# pure_energy.net
KiCad netlist of a schematic drawn in EAGLE
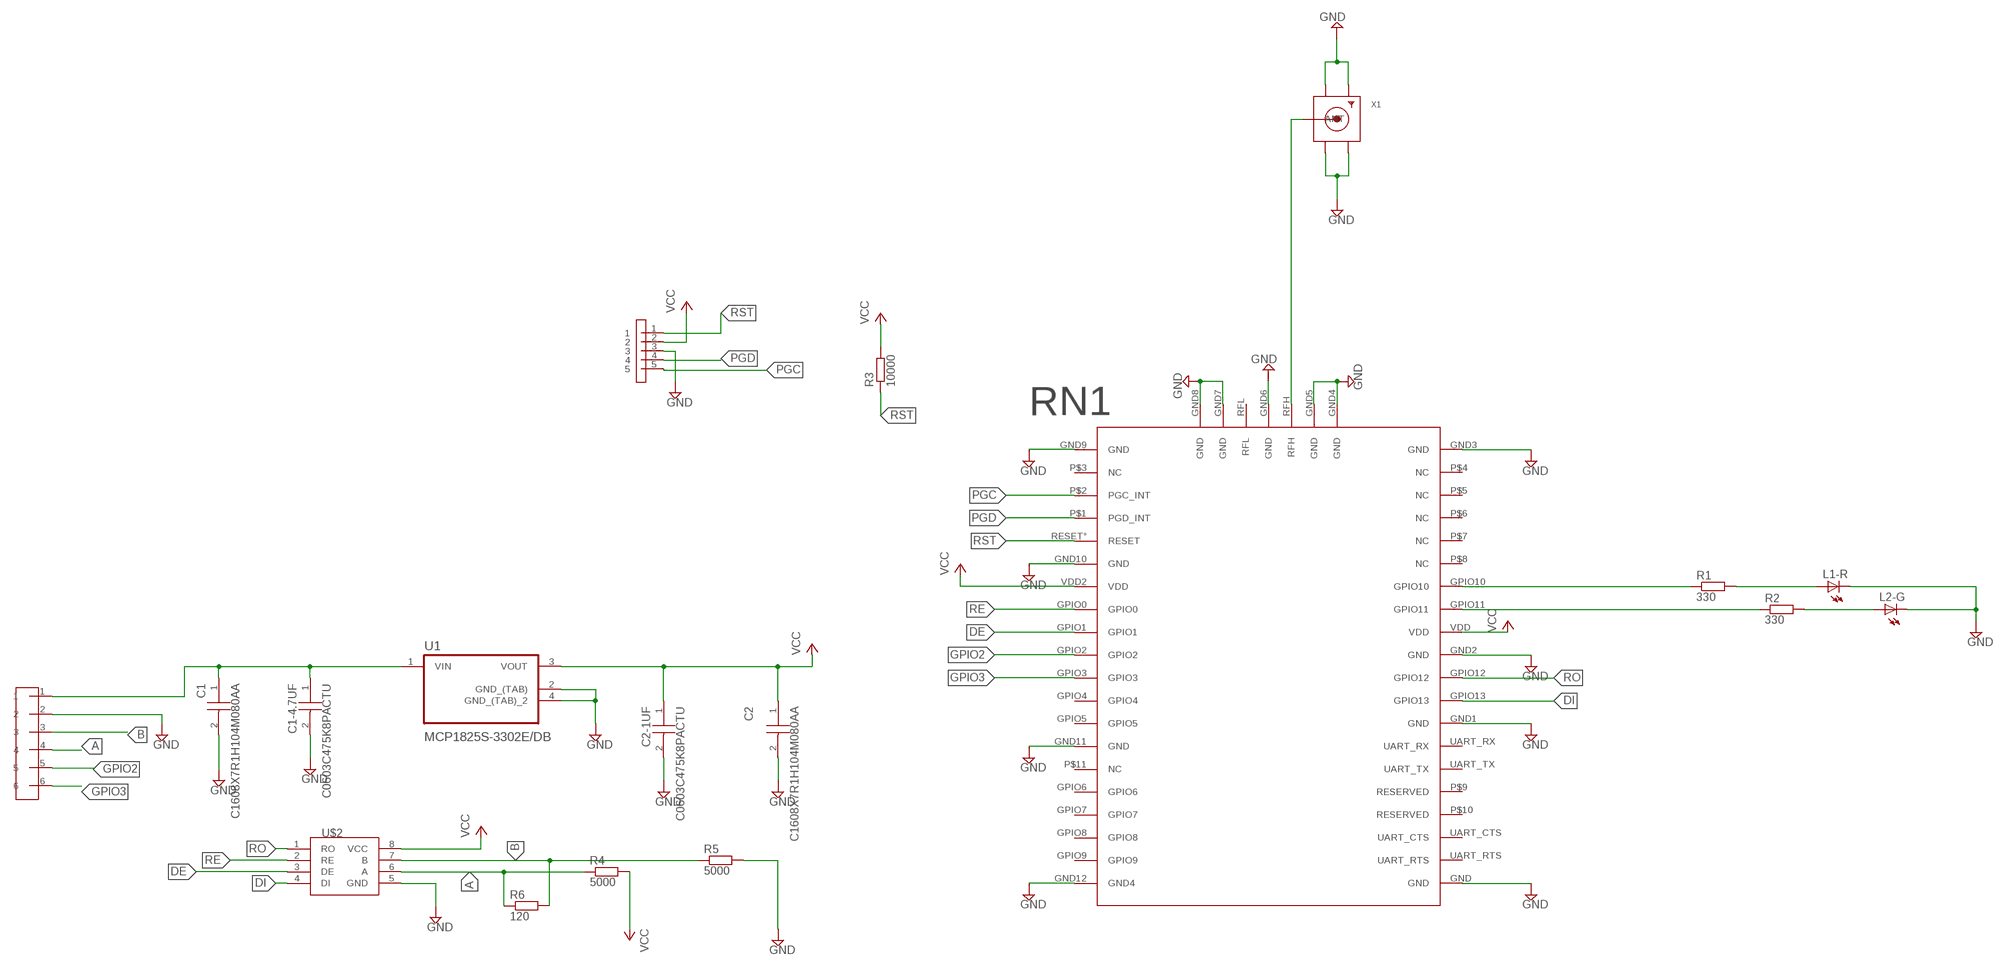
[diagram p0: schematic, sheet 1]

(export (version "E")
  (design (tool "Eeschema 10.0.6"))
  (components
    (comp (ref "C1")
      (value "C1608X7R1H104M080AA")
      (footprint "eagle-import:CAPC1608X80N")
      (fields (field (name "MOUSER_PART_NUMBER") "810-C1608X7R1H104M"))
      (libsource (lib "eagle-import") (part "C1608X7R1H104M080AA"))
    )
    (comp (ref "C1-4.7UF")
      (value "C0603C475K8PACTU")
      (footprint "eagle-import:CAPC1608X85N")
      (fields (field (name "MOUSER_PART_NUMBER") "80-C0603C475K8P"))
      (libsource (lib "eagle-import") (part "C0603C475K8PACTU"))
    )
    (comp (ref "C2")
      (value "C1608X7R1H104M080AA")
      (footprint "eagle-import:CAPC1608X80N")
      (fields (field (name "MOUSER_PART_NUMBER") "810-C1608X7R1H104M"))
      (libsource (lib "eagle-import") (part "C1608X7R1H104M080AA"))
    )
    (comp (ref "C2-1UF")
      (value "C0603C475K8PACTU")
      (footprint "eagle-import:CAPC1608X85N")
      (fields (field (name "MOUSER_PART_NUMBER") "80-C0603C475K8P"))
      (libsource (lib "eagle-import") (part "C0603C475K8PACTU"))
    )
    (comp (ref "L1-R")
      (value "LEDCHIP-LED0603")
      (footprint "eagle-import:CHIP-LED0603")
      (libsource (lib "eagle-import") (part "LEDCHIP-LED0603"))
    )
    (comp (ref "L2-G")
      (value "LEDCHIP-LED0603")
      (footprint "eagle-import:CHIP-LED0603")
      (libsource (lib "eagle-import") (part "LEDCHIP-LED0603"))
    )
    (comp (ref "R1")
      (value "330")
      (footprint "eagle-import:R0603")
      (libsource (lib "eagle-import") (part "R-EU_R0603"))
    )
    (comp (ref "R2")
      (value "330")
      (footprint "eagle-import:R0603")
      (libsource (lib "eagle-import") (part "R-EU_R0603"))
    )
    (comp (ref "R3")
      (value "10000")
      (footprint "eagle-import:R0603")
      (libsource (lib "eagle-import") (part "R-EU_R0603"))
    )
    (comp (ref "R4")
      (value "5000")
      (footprint "eagle-import:R0805")
      (libsource (lib "eagle-import") (part "R-EU_R0805"))
    )
    (comp (ref "R5")
      (value "5000")
      (footprint "eagle-import:R0805")
      (libsource (lib "eagle-import") (part "R-EU_R0805"))
    )
    (comp (ref "R6")
      (value "120")
      (footprint "eagle-import:R0805")
      (libsource (lib "eagle-import") (part "R-EU_R0805"))
    )
    (comp (ref "RN1")
      (value "NEW_RN2483")
      (footprint "eagle-import:NEW_RN2483")
      (libsource (lib "eagle-import") (part "NEW_RN2483"))
    )
    (comp (ref "U$1")
      (value "CONNECTOR62")
      (footprint "eagle-import:CONNECTOR6")
      (libsource (lib "eagle-import") (part "CONNECTOR62"))
    )
    (comp (ref "U$2")
      (value "AMD3485E")
      (footprint "eagle-import:AMD3485E")
      (libsource (lib "eagle-import") (part "AMD3485E"))
    )
    (comp (ref "U$3")
      (value "ICSP52")
      (footprint "eagle-import:ICSP")
      (libsource (lib "eagle-import") (part "ICSP52"))
    )
    (comp (ref "U1")
      (value "MCP1825S-3302E/DB")
      (footprint "eagle-import:SOT230P700X180-4N")
      (fields (field (name "MF") "Microchip"))
      (libsource (lib "eagle-import") (part "MCP1825S-3302E/DB"))
    )
    (comp (ref "X1")
      (value "SMACONNECTOR_EDGE")
      (footprint "eagle-import:SMA_EDGELAUNCH")
      (libsource (lib "eagle-import") (part "SMACONNECTOR_EDGE"))
    )
  )
  (nets
    (net (code "1") (name "A") (class "Default")
      (node (ref "R4") (pin "1") (pinfunction "1_1") (pintype "passive"))
      (node (ref "R6") (pin "1") (pinfunction "1_1") (pintype "passive"))
      (node (ref "U$1") (pin "4") (pinfunction "4_4") (pintype "bidirectional"))
      (node (ref "U$2") (pin "6") (pinfunction "A_6") (pintype "bidirectional"))
    )
    (net (code "2") (name "B") (class "Default")
      (node (ref "R5") (pin "1") (pinfunction "1_1") (pintype "passive"))
      (node (ref "R6") (pin "2") (pinfunction "2_2") (pintype "passive"))
      (node (ref "U$1") (pin "3") (pinfunction "3_3") (pintype "bidirectional"))
      (node (ref "U$2") (pin "7") (pinfunction "B_7") (pintype "bidirectional"))
    )
    (net (code "3") (name "DE") (class "Default")
      (node (ref "RN1") (pin "GPIO1") (pinfunction "GPIO1_GPIO1") (pintype "bidirectional"))
      (node (ref "U$2") (pin "3") (pinfunction "DE_3") (pintype "bidirectional"))
    )
    (net (code "4") (name "DI") (class "Default")
      (node (ref "RN1") (pin "GPIO13") (pinfunction "GPIO13_GPIO13") (pintype "bidirectional"))
      (node (ref "U$2") (pin "4") (pinfunction "DI_4") (pintype "bidirectional"))
    )
    (net (code "5") (name "GND") (class "Default")
      (node (ref "C1") (pin "2") (pinfunction "2_2") (pintype "bidirectional"))
      (node (ref "C1-4.7UF") (pin "2") (pinfunction "C2_2") (pintype "bidirectional"))
      (node (ref "C2") (pin "2") (pinfunction "2_2") (pintype "bidirectional"))
      (node (ref "C2-1UF") (pin "2") (pinfunction "C2_2") (pintype "bidirectional"))
      (node (ref "L1-R") (pin "C") (pinfunction "C_C") (pintype "passive"))
      (node (ref "L2-G") (pin "C") (pinfunction "C_C") (pintype "passive"))
      (node (ref "R5") (pin "2") (pinfunction "2_2") (pintype "passive"))
      (node (ref "RN1") (pin "GND") (pinfunction "GND_GND") (pintype "bidirectional"))
      (node (ref "RN1") (pin "GND1") (pinfunction "GND_GND1") (pintype "bidirectional"))
      (node (ref "RN1") (pin "GND10") (pinfunction "GND_GND10") (pintype "bidirectional"))
      (node (ref "RN1") (pin "GND11") (pinfunction "GND_GND11") (pintype "bidirectional"))
      (node (ref "RN1") (pin "GND12") (pinfunction "GND4_GND12") (pintype "bidirectional"))
      (node (ref "RN1") (pin "GND2") (pinfunction "GND_GND2") (pintype "bidirectional"))
      (node (ref "RN1") (pin "GND3") (pinfunction "GND_GND3") (pintype "bidirectional"))
      (node (ref "RN1") (pin "GND4") (pinfunction "GND_GND4") (pintype "bidirectional"))
      (node (ref "RN1") (pin "GND5") (pinfunction "GND_GND5") (pintype "bidirectional"))
      (node (ref "RN1") (pin "GND6") (pinfunction "GND_GND6") (pintype "bidirectional"))
      (node (ref "RN1") (pin "GND7") (pinfunction "GND_GND7") (pintype "bidirectional"))
      (node (ref "RN1") (pin "GND8") (pinfunction "GND_GND8") (pintype "bidirectional"))
      (node (ref "RN1") (pin "GND9") (pinfunction "GND_GND9") (pintype "bidirectional"))
      (node (ref "U$1") (pin "2") (pinfunction "2_2") (pintype "bidirectional"))
      (node (ref "U$2") (pin "5") (pinfunction "GND_5") (pintype "bidirectional"))
      (node (ref "U$3") (pin "3") (pinfunction "3_3") (pintype "bidirectional"))
      (node (ref "U1") (pin "2") (pinfunction "GND_(TAB)_2") (pintype "power_in"))
      (node (ref "U1") (pin "4") (pinfunction "GND_(TAB)_2_4") (pintype "power_in"))
      (node (ref "X1") (pin "GND@1") (pinfunction "GND4_GND@1") (pintype "power_in"))
      (node (ref "X1") (pin "GND@2") (pinfunction "GND3_GND@2") (pintype "power_in"))
      (node (ref "X1") (pin "GND@3") (pinfunction "GND2_GND@3") (pintype "power_in"))
      (node (ref "X1") (pin "GND@4") (pinfunction "GND1_GND@4") (pintype "power_in"))
    )
    (net (code "6") (name "GPIO2") (class "Default")
      (node (ref "RN1") (pin "GPIO2") (pinfunction "GPIO2_GPIO2") (pintype "bidirectional"))
      (node (ref "U$1") (pin "5") (pinfunction "5_5") (pintype "bidirectional"))
    )
    (net (code "7") (name "GPIO3") (class "Default")
      (node (ref "RN1") (pin "GPIO3") (pinfunction "GPIO3_GPIO3") (pintype "bidirectional"))
      (node (ref "U$1") (pin "6") (pinfunction "6_6") (pintype "bidirectional"))
    )
    (net (code "8") (name "Net-(C1-4.7UF-C1)") (class "Default")
      (node (ref "C1") (pin "1") (pinfunction "1_1") (pintype "bidirectional"))
      (node (ref "C1-4.7UF") (pin "1") (pinfunction "C1_1") (pintype "bidirectional"))
      (node (ref "U$1") (pin "1") (pinfunction "1_1") (pintype "bidirectional"))
      (node (ref "U1") (pin "1") (pinfunction "VIN_1") (pintype "input"))
    )
    (net (code "9") (name "Net-(L1-R-PadA)") (class "Default")
      (node (ref "L1-R") (pin "A") (pinfunction "A_A") (pintype "passive"))
      (node (ref "R1") (pin "2") (pinfunction "2_2") (pintype "passive"))
    )
    (net (code "10") (name "Net-(L2-G-PadA)") (class "Default")
      (node (ref "L2-G") (pin "A") (pinfunction "A_A") (pintype "passive"))
      (node (ref "R2") (pin "2") (pinfunction "2_2") (pintype "passive"))
    )
    (net (code "11") (name "Net-(R1-Pad1)") (class "Default")
      (node (ref "R1") (pin "1") (pinfunction "1_1") (pintype "passive"))
      (node (ref "RN1") (pin "GPIO10") (pinfunction "GPIO10_GPIO10") (pintype "bidirectional"))
    )
    (net (code "12") (name "Net-(R2-Pad1)") (class "Default")
      (node (ref "R2") (pin "1") (pinfunction "1_1") (pintype "passive"))
      (node (ref "RN1") (pin "GPIO11") (pinfunction "GPIO11_GPIO11") (pintype "bidirectional"))
    )
    (net (code "13") (name "Net-(X1-ANT)") (class "Default")
      (node (ref "RN1") (pin "RFH") (pinfunction "RFH_RFH") (pintype "bidirectional"))
      (node (ref "X1") (pin "P") (pinfunction "ANT_P") (pintype "bidirectional"))
    )
    (net (code "14") (name "PGC") (class "Default")
      (node (ref "RN1") (pin "P$2") (pinfunction "PGC_INT_P$2") (pintype "bidirectional"))
      (node (ref "U$3") (pin "5") (pinfunction "5_5") (pintype "bidirectional"))
    )
    (net (code "15") (name "PGD") (class "Default")
      (node (ref "RN1") (pin "P$1") (pinfunction "PGD_INT_P$1") (pintype "bidirectional"))
      (node (ref "U$3") (pin "4") (pinfunction "4_4") (pintype "bidirectional"))
    )
    (net (code "16") (name "RE") (class "Default")
      (node (ref "RN1") (pin "GPIO0") (pinfunction "GPIO0_GPIO0") (pintype "bidirectional"))
      (node (ref "U$2") (pin "2") (pinfunction "RE_2") (pintype "bidirectional"))
    )
    (net (code "17") (name "RO") (class "Default")
      (node (ref "RN1") (pin "GPIO12") (pinfunction "GPIO12_GPIO12") (pintype "bidirectional"))
      (node (ref "U$2") (pin "1") (pinfunction "RO_1") (pintype "bidirectional"))
    )
    (net (code "18") (name "RST") (class "Default")
      (node (ref "R3") (pin "1") (pinfunction "1_1") (pintype "passive"))
      (node (ref "RN1") (pin "RESET°") (pinfunction "RESET_RESET°") (pintype "bidirectional"))
      (node (ref "U$3") (pin "1") (pinfunction "1_1") (pintype "bidirectional"))
    )
    (net (code "19") (name "VCC") (class "Default")
      (node (ref "C2") (pin "1") (pinfunction "1_1") (pintype "bidirectional"))
      (node (ref "C2-1UF") (pin "1") (pinfunction "C1_1") (pintype "bidirectional"))
      (node (ref "R3") (pin "2") (pinfunction "2_2") (pintype "passive"))
      (node (ref "R4") (pin "2") (pinfunction "2_2") (pintype "passive"))
      (node (ref "RN1") (pin "VDD") (pinfunction "VDD_VDD") (pintype "bidirectional"))
      (node (ref "RN1") (pin "VDD2") (pinfunction "VDD_VDD2") (pintype "bidirectional"))
      (node (ref "U$2") (pin "8") (pinfunction "VCC_8") (pintype "bidirectional"))
      (node (ref "U$3") (pin "2") (pinfunction "2_2") (pintype "bidirectional"))
      (node (ref "U1") (pin "3") (pinfunction "VOUT_3") (pintype "output"))
    )
    (net (code "20") (name "unconnected-(RN1-NC-PadP$3)") (class "Default")
      (node (ref "RN1") (pin "P$3") (pinfunction "NC_P$3") (pintype "bidirectional"))
    )
    (net (code "21") (name "unconnected-(RN1-NC-PadP$4)") (class "Default")
      (node (ref "RN1") (pin "P$4") (pinfunction "NC_P$4") (pintype "bidirectional"))
    )
    (net (code "22") (name "unconnected-(RN1-NC-PadP$5)") (class "Default")
      (node (ref "RN1") (pin "P$5") (pinfunction "NC_P$5") (pintype "bidirectional"))
    )
    (net (code "23") (name "unconnected-(RN1-NC-PadP$6)") (class "Default")
      (node (ref "RN1") (pin "P$6") (pinfunction "NC_P$6") (pintype "bidirectional"))
    )
    (net (code "24") (name "unconnected-(RN1-NC-PadP$7)") (class "Default")
      (node (ref "RN1") (pin "P$7") (pinfunction "NC_P$7") (pintype "bidirectional"))
    )
    (net (code "25") (name "unconnected-(RN1-NC-PadP$8)") (class "Default")
      (node (ref "RN1") (pin "P$8") (pinfunction "NC_P$8") (pintype "bidirectional"))
    )
    (net (code "26") (name "unconnected-(RN1-NC-PadP$11)") (class "Default")
      (node (ref "RN1") (pin "P$11") (pinfunction "NC_P$11") (pintype "bidirectional"))
    )
    (net (code "27") (name "unconnected-(RN1-PadGPIO4)") (class "Default")
      (node (ref "RN1") (pin "GPIO4") (pinfunction "GPIO4_GPIO4") (pintype "bidirectional"))
    )
    (net (code "28") (name "unconnected-(RN1-PadGPIO5)") (class "Default")
      (node (ref "RN1") (pin "GPIO5") (pinfunction "GPIO5_GPIO5") (pintype "bidirectional"))
    )
    (net (code "29") (name "unconnected-(RN1-PadGPIO6)") (class "Default")
      (node (ref "RN1") (pin "GPIO6") (pinfunction "GPIO6_GPIO6") (pintype "bidirectional"))
    )
    (net (code "30") (name "unconnected-(RN1-PadGPIO7)") (class "Default")
      (node (ref "RN1") (pin "GPIO7") (pinfunction "GPIO7_GPIO7") (pintype "bidirectional"))
    )
    (net (code "31") (name "unconnected-(RN1-PadGPIO8)") (class "Default")
      (node (ref "RN1") (pin "GPIO8") (pinfunction "GPIO8_GPIO8") (pintype "bidirectional"))
    )
    (net (code "32") (name "unconnected-(RN1-PadGPIO9)") (class "Default")
      (node (ref "RN1") (pin "GPIO9") (pinfunction "GPIO9_GPIO9") (pintype "bidirectional"))
    )
    (net (code "33") (name "unconnected-(RN1-PadRFL)") (class "Default")
      (node (ref "RN1") (pin "RFL") (pinfunction "RFL_RFL") (pintype "bidirectional"))
    )
    (net (code "34") (name "unconnected-(RN1-PadUART_CTS)") (class "Default")
      (node (ref "RN1") (pin "UART_CTS") (pinfunction "UART_CTS_UART_CTS") (pintype "bidirectional"))
    )
    (net (code "35") (name "unconnected-(RN1-PadUART_RTS)") (class "Default")
      (node (ref "RN1") (pin "UART_RTS") (pinfunction "UART_RTS_UART_RTS") (pintype "bidirectional"))
    )
    (net (code "36") (name "unconnected-(RN1-PadUART_RX)") (class "Default")
      (node (ref "RN1") (pin "UART_RX") (pinfunction "UART_RX_UART_RX") (pintype "bidirectional"))
    )
    (net (code "37") (name "unconnected-(RN1-PadUART_TX)") (class "Default")
      (node (ref "RN1") (pin "UART_TX") (pinfunction "UART_TX_UART_TX") (pintype "bidirectional"))
    )
    (net (code "38") (name "unconnected-(RN1-RESERVED-PadP$9)") (class "Default")
      (node (ref "RN1") (pin "P$9") (pinfunction "RESERVED_P$9") (pintype "bidirectional"))
    )
    (net (code "39") (name "unconnected-(RN1-RESERVED-PadP$10)") (class "Default")
      (node (ref "RN1") (pin "P$10") (pinfunction "RESERVED_P$10") (pintype "bidirectional"))
    )
  )
)
